# Imx6ull.net
KiCad netlist of a schematic drawn in Altium Designer
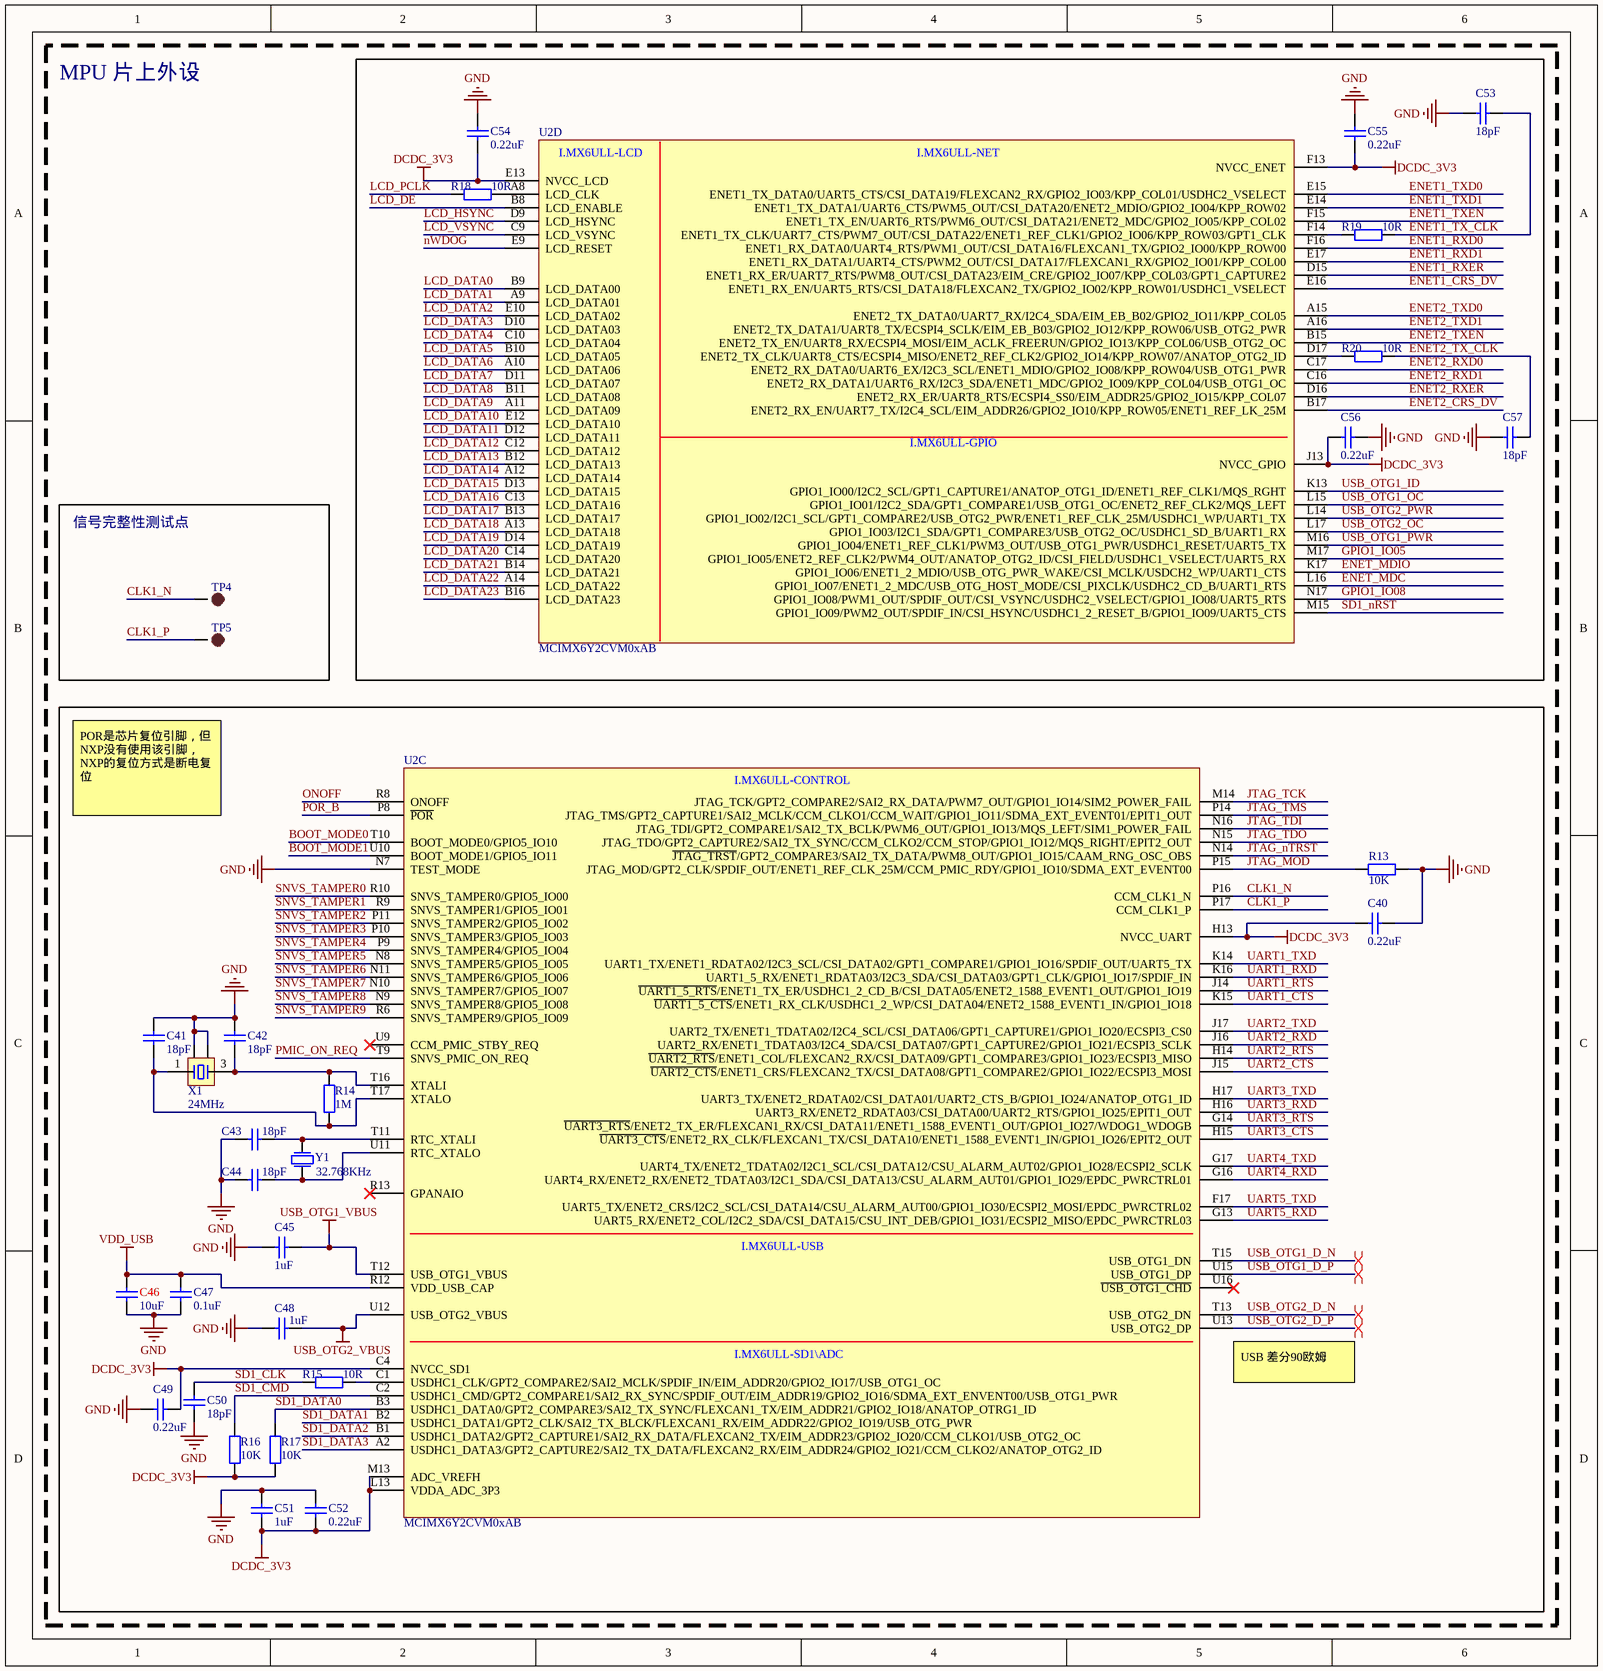
[diagram p0: Imx6ull.SchDoc]

(export (version "E")
  (design (tool "Eeschema 10.0.6"))
  (components
    (comp (ref "C40")
      (value "0.22uF")
      (footprint "0402_C")
      (description "贴片电容")
      (libsource (lib "My_Devices") (part "0402_C"))
    )
    (comp (ref "C41")
      (value "18pF")
      (footprint "0402_C")
      (description "贴片电容")
      (libsource (lib "My_Devices") (part "0402_C"))
    )
    (comp (ref "C42")
      (value "18pF")
      (footprint "0402_C")
      (description "贴片电容")
      (libsource (lib "My_Devices") (part "0402_C"))
    )
    (comp (ref "C43")
      (value "18pF")
      (footprint "0402_C")
      (description "贴片电容")
      (libsource (lib "My_Devices") (part "0402_C"))
    )
    (comp (ref "C44")
      (value "18pF")
      (footprint "0402_C")
      (description "贴片电容")
      (libsource (lib "My_Devices") (part "0402_C"))
    )
    (comp (ref "C45")
      (value "1uF")
      (footprint "0402_C")
      (description "贴片电容")
      (libsource (lib "My_Devices") (part "0402_C"))
    )
    (comp (ref "C46")
      (value "10uF")
      (footprint "0603_C _MINI")
      (description "贴片电容")
      (libsource (lib "My_Devices") (part "0603_C_MINI"))
    )
    (comp (ref "C47")
      (value "0.1uF")
      (footprint "0402_C")
      (description "贴片电容")
      (libsource (lib "My_Devices") (part "0402_C"))
    )
    (comp (ref "C48")
      (value "1uF")
      (footprint "0402_C")
      (description "贴片电容")
      (libsource (lib "My_Devices") (part "0402_C"))
    )
    (comp (ref "C49")
      (value "0.22uF")
      (footprint "0402_C")
      (description "贴片电容")
      (libsource (lib "My_Devices") (part "0402_C"))
    )
    (comp (ref "C50")
      (value "18pF")
      (footprint "0402_C")
      (description "贴片电容")
      (libsource (lib "My_Devices") (part "0402_C"))
    )
    (comp (ref "C51")
      (value "1uF")
      (footprint "0402_C")
      (description "贴片电容")
      (libsource (lib "My_Devices") (part "0402_C"))
    )
    (comp (ref "C52")
      (value "0.22uF")
      (footprint "0402_C")
      (description "贴片电容")
      (libsource (lib "My_Devices") (part "0402_C"))
    )
    (comp (ref "C53")
      (value "18pF")
      (footprint "0402_C")
      (description "贴片电容")
      (libsource (lib "My_Devices") (part "0402_C"))
    )
    (comp (ref "C54")
      (value "0.22uF")
      (footprint "0402_C")
      (description "贴片电容")
      (libsource (lib "My_Devices") (part "0402_C"))
    )
    (comp (ref "C55")
      (value "0.22uF")
      (footprint "0402_C")
      (description "贴片电容")
      (libsource (lib "My_Devices") (part "0402_C"))
    )
    (comp (ref "C56")
      (value "0.22uF")
      (footprint "0402_C")
      (description "贴片电容")
      (libsource (lib "My_Devices") (part "0402_C"))
    )
    (comp (ref "C57")
      (value "18pF")
      (footprint "0402_C")
      (description "贴片电容")
      (libsource (lib "My_Devices") (part "0402_C"))
    )
    (comp (ref "R13")
      (value "10K")
      (footprint "0402_R")
      (description "贴片电阻")
      (libsource (lib "My_Devices") (part "0402_R"))
    )
    (comp (ref "R14")
      (value "1M")
      (footprint "0402_R")
      (description "贴片电阻")
      (libsource (lib "") (part "0402_R_1"))
    )
    (comp (ref "R15")
      (value "10R")
      (footprint "0402_R")
      (description "贴片电阻")
      (libsource (lib "My_Devices") (part "0402_R"))
    )
    (comp (ref "R16")
      (value "10K")
      (footprint "0402_R")
      (description "贴片电阻")
      (libsource (lib "") (part "0402_R_2"))
    )
    (comp (ref "R17")
      (value "10K")
      (footprint "0402_R")
      (description "贴片电阻")
      (libsource (lib "") (part "0402_R_2"))
    )
    (comp (ref "R18")
      (value "10R")
      (footprint "0402_R")
      (description "贴片电阻")
      (libsource (lib "My_Devices") (part "0402_R"))
    )
    (comp (ref "R19")
      (value "10R")
      (footprint "0402_R")
      (description "贴片电阻")
      (libsource (lib "My_Devices") (part "0402_R"))
    )
    (comp (ref "R20")
      (value "10R")
      (footprint "0402_R")
      (description "贴片电阻")
      (libsource (lib "My_Devices") (part "0402_R"))
    )
    (comp (ref "TP4")
      (value "SOC_IN")
      (footprint "TP-1.0")
      (description "测试点")
      (libsource (lib "Linux_Base") (part "TEST-POINT"))
    )
    (comp (ref "TP5")
      (value "SOC_IN")
      (footprint "TP-1.0")
      (description "测试点")
      (libsource (lib "Linux_Base") (part "TEST-POINT"))
    )
    (comp (ref "U2")
      (value "MCIMX6Y2CVM0xAB")
      (footprint "BGA289_17x17_0.8Pitch")
      (libsource (lib "") (part "MCIMX6Y2CVM0xAB_1"))
    )
    (comp (ref "X1")
      (value "24MHz")
      (footprint "OSC 3225-4P")
      (description "4脚无源晶振")
      (fields (field (name "版权归属") "源创客"))
      (libsource (lib "My_Devices") (part "XTAL-4P"))
    )
    (comp (ref "Y1")
      (value "32.768KHz")
      (footprint "OSC 3215-2P")
      (description "2脚无源晶振")
      (libsource (lib "My_Devices") (part "XTAL-2P"))
    )
  )
  (nets
    (net (code "1") (name "/BOOT_MODE0") (class "Default")
      (node (ref "U2") (pin "T10") (pinfunction "BOOT_MODE0/GPIO5_IO10_T10") (pintype "passive"))
    )
    (net (code "2") (name "/BOOT_MODE1") (class "Default")
      (node (ref "U2") (pin "U10") (pinfunction "BOOT_MODE1/GPIO5_IO11_U10") (pintype "passive"))
    )
    (net (code "3") (name "/CLK1_N") (class "Default")
      (node (ref "TP4") (pin "1") (pinfunction "1_1") (pintype "passive"))
      (node (ref "U2") (pin "P16") (pinfunction "CCM_CLK1_N_P16") (pintype "passive"))
    )
    (net (code "4") (name "/CLK1_P") (class "Default")
      (node (ref "TP5") (pin "1") (pinfunction "1_1") (pintype "passive"))
      (node (ref "U2") (pin "P17") (pinfunction "CCM_CLK1_P_P17") (pintype "passive"))
    )
    (net (code "5") (name "/ENET1_CRS_DV") (class "Default")
      (node (ref "U2") (pin "E16") (pinfunction "ENET1_RX_EN/UART5_RTS/CSI_DATA18/FLEXCAN2_TX/GPIO2_IO02/KPP_ROW01/USDHC1_VSELECT_E16") (pintype "passive"))
    )
    (net (code "6") (name "/ENET1_RXD0") (class "Default")
      (node (ref "U2") (pin "F16") (pinfunction "ENET1_RX_DATA0/UART4_RTS/PWM1_OUT/CSI_DATA16/FLEXCAN1_TX/GPIO2_IO00/KPP_ROW00_F16") (pintype "passive"))
    )
    (net (code "7") (name "/ENET1_RXD1") (class "Default")
      (node (ref "U2") (pin "E17") (pinfunction "ENET1_RX_DATA1/UART4_CTS/PWM2_OUT/CSI_DATA17/FLEXCAN1_RX/GPIO2_IO01/KPP_COL00_E17") (pintype "passive"))
    )
    (net (code "8") (name "/ENET1_RXER") (class "Default")
      (node (ref "U2") (pin "D15") (pinfunction "ENET1_RX_ER/UART7_RTS/PWM8_OUT/CSI_DATA23/EIM_CRE/GPIO2_IO07/KPP_COL03/GPT1_CAPTURE2_D15") (pintype "passive"))
    )
    (net (code "9") (name "/ENET1_TXD0") (class "Default")
      (node (ref "U2") (pin "E15") (pinfunction "ENET1_TX_DATA0/UART5_CTS/CSI_DATA19/FLEXCAN2_RX/GPIO2_IO03/KPP_COL01/USDHC2_VSELECT_E15") (pintype "passive"))
    )
    (net (code "10") (name "/ENET1_TXD1") (class "Default")
      (node (ref "U2") (pin "E14") (pinfunction "ENET1_TX_DATA1/UART6_CTS/PWM5_OUT/CSI_DATA20/ENET2_MDIO/GPIO2_IO04/KPP_ROW02_E14") (pintype "passive"))
    )
    (net (code "11") (name "/ENET1_TXEN") (class "Default")
      (node (ref "U2") (pin "F15") (pinfunction "ENET1_TX_EN/UART6_RTS/PWM6_OUT/CSI_DATA21/ENET2_MDC/GPIO2_IO05/KPP_COL02_F15") (pintype "passive"))
    )
    (net (code "12") (name "/ENET1_TX_CLK") (class "Default")
      (node (ref "C53") (pin "1") (pinfunction "1_1") (pintype "passive"))
      (node (ref "R19") (pin "2") (pinfunction "2_2") (pintype "passive"))
    )
    (net (code "13") (name "/ENET2_CRS_DV") (class "Default")
      (node (ref "U2") (pin "B17") (pinfunction "ENET2_RX_EN/UART7_TX/I2C4_SCL/EIM_ADDR26/GPIO2_IO10/KPP_ROW05/ENET1_REF_LK_25M_B17") (pintype "passive"))
    )
    (net (code "14") (name "/ENET2_RXD0") (class "Default")
      (node (ref "U2") (pin "C17") (pinfunction "ENET2_RX_DATA0/UART6_EX/I2C3_SCL/ENET1_MDIO/GPIO2_IO08/KPP_ROW04/USB_OTG1_PWR_C17") (pintype "passive"))
    )
    (net (code "15") (name "/ENET2_RXD1") (class "Default")
      (node (ref "U2") (pin "C16") (pinfunction "ENET2_RX_DATA1/UART6_RX/I2C3_SDA/ENET1_MDC/GPIO2_IO09/KPP_COL04/USB_OTG1_OC_C16") (pintype "passive"))
    )
    (net (code "16") (name "/ENET2_RXER") (class "Default")
      (node (ref "U2") (pin "D16") (pinfunction "ENET2_RX_ER/UART8_RTS/ECSPI4_SS0/EIM_ADDR25/GPIO2_IO15/KPP_COL07_D16") (pintype "passive"))
    )
    (net (code "17") (name "/ENET2_TXD0") (class "Default")
      (node (ref "U2") (pin "A15") (pinfunction "ENET2_TX_DATA0/UART7_RX/I2C4_SDA/EIM_EB_B02/GPIO2_IO11/KPP_COL05_A15") (pintype "passive"))
    )
    (net (code "18") (name "/ENET2_TXD1") (class "Default")
      (node (ref "U2") (pin "A16") (pinfunction "ENET2_TX_DATA1/UART8_TX/ECSPI4_SCLK/EIM_EB_B03/GPIO2_IO12/KPP_ROW06/USB_OTG2_PWR_A16") (pintype "passive"))
    )
    (net (code "19") (name "/ENET2_TXEN") (class "Default")
      (node (ref "U2") (pin "B15") (pinfunction "ENET2_TX_EN/UART8_RX/ECSPI4_MOSI/EIM_ACLK_FREERUN/GPIO2_IO13/KPP_COL06/USB_OTG2_OC_B15") (pintype "passive"))
    )
    (net (code "20") (name "/ENET2_TX_CLK") (class "Default")
      (node (ref "C57") (pin "2") (pinfunction "2_2") (pintype "passive"))
      (node (ref "R20") (pin "2") (pinfunction "2_2") (pintype "passive"))
    )
    (net (code "21") (name "/ENET_MDC") (class "Default")
      (node (ref "U2") (pin "L16") (pinfunction "GPIO1_IO07/ENET1_2_MDC/USB_OTG_HOST_MODE/CSI_PIXCLK/USDHC2_CD_B/UART1_RTS_L16") (pintype "passive"))
    )
    (net (code "22") (name "/ENET_MDIO") (class "Default")
      (node (ref "U2") (pin "K17") (pinfunction "GPIO1_IO06/ENET1_2_MDIO/USB_OTG_PWR_WAKE/CSI_MCLK/USDCH2_WP/UART1_CTS_K17") (pintype "passive"))
    )
    (net (code "23") (name "/GPIO1_IO05") (class "Default")
      (node (ref "U2") (pin "M17") (pinfunction "GPIO1_IO05/ENET2_REF_CLK2/PWM4_OUT/ANATOP_OTG2_ID/CSI_FIELD/USDHC1_VSELECT/UART5_RX_M17") (pintype "passive"))
    )
    (net (code "24") (name "/GPIO1_IO08") (class "Default")
      (node (ref "U2") (pin "N17") (pinfunction "GPIO1_IO08/PWM1_OUT/SPDIF_OUT/CSI_VSYNC/USDHC2_VSELECT/GPIO1_IO08/UART5_RTS_N17") (pintype "passive"))
    )
    (net (code "25") (name "/JTAG_MOD") (class "Default")
      (node (ref "R13") (pin "1") (pinfunction "1_1") (pintype "passive"))
      (node (ref "U2") (pin "P15") (pinfunction "JTAG_MOD/GPT2_CLK/SPDIF_OUT/ENET1_REF_CLK_25M/CCM_PMIC_RDY/GPIO1_IO10/SDMA_EXT_EVENT00_P15") (pintype "passive"))
    )
    (net (code "26") (name "/JTAG_TCK") (class "Default")
      (node (ref "U2") (pin "M14") (pinfunction "JTAG_TCK/GPT2_COMPARE2/SAI2_RX_DATA/PWM7_OUT/GPIO1_IO14/SIM2_POWER_FAIL_M14") (pintype "passive"))
    )
    (net (code "27") (name "/JTAG_TDI") (class "Default")
      (node (ref "U2") (pin "N16") (pinfunction "JTAG_TDI/GPT2_COMPARE1/SAI2_TX_BCLK/PWM6_OUT/GPIO1_IO13/MQS_LEFT/SIM1_POWER_FAIL_N16") (pintype "passive"))
    )
    (net (code "28") (name "/JTAG_TDO") (class "Default")
      (node (ref "U2") (pin "N15") (pinfunction "JTAG_TDO/GPT2_CAPTURE2/SAI2_TX_SYNC/CCM_CLKO2/CCM_STOP/GPIO1_IO12/MQS_RIGHT/EPIT2_OUT_N15") (pintype "passive"))
    )
    (net (code "29") (name "/JTAG_TMS") (class "Default")
      (node (ref "U2") (pin "P14") (pinfunction "JTAG_TMS/GPT2_CAPTURE1/SAI2_MCLK/CCM_CLKO1/CCM_WAIT/GPIO1_IO11/SDMA_EXT_EVENT01/EPIT1_OUT_P14") (pintype "passive"))
    )
    (net (code "30") (name "/JTAG_nTRST") (class "Default")
      (node (ref "U2") (pin "N14") (pinfunction "~{JTAG_TRST}/GPT2_COMPARE3/SAI2_TX_DATA/PWM8_OUT/GPIO1_IO15/CAAM_RNG_OSC_OBS_N14") (pintype "passive"))
    )
    (net (code "31") (name "/LCD_DATA0") (class "Default")
      (node (ref "U2") (pin "B9") (pinfunction "LCD_DATA00_B9") (pintype "passive"))
    )
    (net (code "32") (name "/LCD_DATA1") (class "Default")
      (node (ref "U2") (pin "A9") (pinfunction "LCD_DATA01_A9") (pintype "passive"))
    )
    (net (code "33") (name "/LCD_DATA2") (class "Default")
      (node (ref "U2") (pin "E10") (pinfunction "LCD_DATA02_E10") (pintype "passive"))
    )
    (net (code "34") (name "/LCD_DATA3") (class "Default")
      (node (ref "U2") (pin "D10") (pinfunction "LCD_DATA03_D10") (pintype "passive"))
    )
    (net (code "35") (name "/LCD_DATA4") (class "Default")
      (node (ref "U2") (pin "C10") (pinfunction "LCD_DATA04_C10") (pintype "passive"))
    )
    (net (code "36") (name "/LCD_DATA5") (class "Default")
      (node (ref "U2") (pin "B10") (pinfunction "LCD_DATA05_B10") (pintype "passive"))
    )
    (net (code "37") (name "/LCD_DATA6") (class "Default")
      (node (ref "U2") (pin "A10") (pinfunction "LCD_DATA06_A10") (pintype "passive"))
    )
    (net (code "38") (name "/LCD_DATA7") (class "Default")
      (node (ref "U2") (pin "D11") (pinfunction "LCD_DATA07_D11") (pintype "passive"))
    )
    (net (code "39") (name "/LCD_DATA8") (class "Default")
      (node (ref "U2") (pin "B11") (pinfunction "LCD_DATA08_B11") (pintype "passive"))
    )
    (net (code "40") (name "/LCD_DATA9") (class "Default")
      (node (ref "U2") (pin "A11") (pinfunction "LCD_DATA09_A11") (pintype "passive"))
    )
    (net (code "41") (name "/LCD_DATA10") (class "Default")
      (node (ref "U2") (pin "E12") (pinfunction "LCD_DATA10_E12") (pintype "passive"))
    )
    (net (code "42") (name "/LCD_DATA11") (class "Default")
      (node (ref "U2") (pin "D12") (pinfunction "LCD_DATA11_D12") (pintype "passive"))
    )
    (net (code "43") (name "/LCD_DATA12") (class "Default")
      (node (ref "U2") (pin "C12") (pinfunction "LCD_DATA12_C12") (pintype "passive"))
    )
    (net (code "44") (name "/LCD_DATA13") (class "Default")
      (node (ref "U2") (pin "B12") (pinfunction "LCD_DATA13_B12") (pintype "passive"))
    )
    (net (code "45") (name "/LCD_DATA14") (class "Default")
      (node (ref "U2") (pin "A12") (pinfunction "LCD_DATA14_A12") (pintype "passive"))
    )
    (net (code "46") (name "/LCD_DATA15") (class "Default")
      (node (ref "U2") (pin "D13") (pinfunction "LCD_DATA15_D13") (pintype "passive"))
    )
    (net (code "47") (name "/LCD_DATA16") (class "Default")
      (node (ref "U2") (pin "C13") (pinfunction "LCD_DATA16_C13") (pintype "passive"))
    )
    (net (code "48") (name "/LCD_DATA17") (class "Default")
      (node (ref "U2") (pin "B13") (pinfunction "LCD_DATA17_B13") (pintype "passive"))
    )
    (net (code "49") (name "/LCD_DATA18") (class "Default")
      (node (ref "U2") (pin "A13") (pinfunction "LCD_DATA18_A13") (pintype "passive"))
    )
    (net (code "50") (name "/LCD_DATA19") (class "Default")
      (node (ref "U2") (pin "D14") (pinfunction "LCD_DATA19_D14") (pintype "passive"))
    )
    (net (code "51") (name "/LCD_DATA20") (class "Default")
      (node (ref "U2") (pin "C14") (pinfunction "LCD_DATA20_C14") (pintype "passive"))
    )
    (net (code "52") (name "/LCD_DATA21") (class "Default")
      (node (ref "U2") (pin "B14") (pinfunction "LCD_DATA21_B14") (pintype "passive"))
    )
    (net (code "53") (name "/LCD_DATA22") (class "Default")
      (node (ref "U2") (pin "A14") (pinfunction "LCD_DATA22_A14") (pintype "passive"))
    )
    (net (code "54") (name "/LCD_DATA23") (class "Default")
      (node (ref "U2") (pin "B16") (pinfunction "LCD_DATA23_B16") (pintype "passive"))
    )
    (net (code "55") (name "/LCD_DE") (class "Default")
      (node (ref "U2") (pin "B8") (pinfunction "LCD_ENABLE_B8") (pintype "passive"))
    )
    (net (code "56") (name "/LCD_HSYNC") (class "Default")
      (node (ref "U2") (pin "D9") (pinfunction "LCD_HSYNC_D9") (pintype "passive"))
    )
    (net (code "57") (name "/LCD_PCLK") (class "Default")
      (node (ref "R18") (pin "1") (pinfunction "1_1") (pintype "passive"))
    )
    (net (code "58") (name "/LCD_VSYNC") (class "Default")
      (node (ref "U2") (pin "C9") (pinfunction "LCD_VSYNC_C9") (pintype "passive"))
    )
    (net (code "59") (name "/ONOFF") (class "Default")
      (node (ref "U2") (pin "R8") (pinfunction "ONOFF_R8") (pintype "passive"))
    )
    (net (code "60") (name "/PMIC_ON_REQ") (class "Default")
      (node (ref "U2") (pin "T9") (pinfunction "SNVS_PMIC_ON_REQ_T9") (pintype "passive"))
    )
    (net (code "61") (name "/POR_B") (class "Default")
      (node (ref "U2") (pin "P8") (pinfunction "~{POR}_P8") (pintype "passive"))
    )
    (net (code "62") (name "/SD1_CLK") (class "Default")
      (node (ref "C50") (pin "2") (pinfunction "2_2") (pintype "passive"))
      (node (ref "R15") (pin "1") (pinfunction "1_1") (pintype "passive"))
    )
    (net (code "63") (name "/SD1_CMD") (class "Default")
      (node (ref "R16") (pin "2") (pinfunction "2_2") (pintype "passive"))
      (node (ref "U2") (pin "C2") (pinfunction "USDHC1_CMD/GPT2_COMPARE1/SAI2_RX_SYNC/SPDIF_OUT/EIM_ADDR19/GPIO2_IO16/SDMA_EXT_ENVENT00/USB_OTG1_PWR_C2") (pintype "passive"))
    )
    (net (code "64") (name "/SD1_DATA0") (class "Default")
      (node (ref "R17") (pin "2") (pinfunction "2_2") (pintype "passive"))
      (node (ref "U2") (pin "B3") (pinfunction "USDHC1_DATA0/GPT2_COMPARE3/SAI2_TX_SYNC/FLEXCAN1_TX/EIM_ADDR21/GPIO2_IO18/ANATOP_OTRG1_ID_B3") (pintype "passive"))
    )
    (net (code "65") (name "/SD1_DATA1") (class "Default")
      (node (ref "U2") (pin "B2") (pinfunction "USDHC1_DATA1/GPT2_CLK/SAI2_TX_BLCK/FLEXCAN1_RX/EIM_ADDR22/GPIO2_IO19/USB_OTG_PWR_B2") (pintype "passive"))
    )
    (net (code "66") (name "/SD1_DATA2") (class "Default")
      (node (ref "U2") (pin "B1") (pinfunction "USDHC1_DATA2/GPT2_CAPTURE1/SAI2_RX_DATA/FLEXCAN2_TX/EIM_ADDR23/GPIO2_IO20/CCM_CLKO1/USB_OTG2_OC_B1") (pintype "passive"))
    )
    (net (code "67") (name "/SD1_DATA3") (class "Default")
      (node (ref "U2") (pin "A2") (pinfunction "USDHC1_DATA3/GPT2_CAPTURE2/SAI2_TX_DATA/FLEXCAN2_RX/EIM_ADDR24/GPIO2_IO21/CCM_CLKO2/ANATOP_OTG2_ID_A2") (pintype "passive"))
    )
    (net (code "68") (name "/SD1_nRST") (class "Default")
      (node (ref "U2") (pin "M15") (pinfunction "GPIO1_IO09/PWM2_OUT/SPDIF_IN/CSI_HSYNC/USDHC1_2_RESET_B/GPIO1_IO09/UART5_CTS_M15") (pintype "passive"))
    )
    (net (code "69") (name "/SNVS_TAMPER0") (class "Default")
      (node (ref "U2") (pin "R10") (pinfunction "SNVS_TAMPER0/GPIO5_IO00_R10") (pintype "passive"))
    )
    (net (code "70") (name "/SNVS_TAMPER1") (class "Default")
      (node (ref "U2") (pin "R9") (pinfunction "SNVS_TAMPER1/GPIO5_IO01_R9") (pintype "passive"))
    )
    (net (code "71") (name "/SNVS_TAMPER2") (class "Default")
      (node (ref "U2") (pin "P11") (pinfunction "SNVS_TAMPER2/GPIO5_IO02_P11") (pintype "passive"))
    )
    (net (code "72") (name "/SNVS_TAMPER3") (class "Default")
      (node (ref "U2") (pin "P10") (pinfunction "SNVS_TAMPER3/GPIO5_IO03_P10") (pintype "passive"))
    )
    (net (code "73") (name "/SNVS_TAMPER4") (class "Default")
      (node (ref "U2") (pin "P9") (pinfunction "SNVS_TAMPER4/GPIO5_IO04_P9") (pintype "passive"))
    )
    (net (code "74") (name "/SNVS_TAMPER5") (class "Default")
      (node (ref "U2") (pin "N8") (pinfunction "SNVS_TAMPER5/GPIO5_IO05_N8") (pintype "passive"))
    )
    (net (code "75") (name "/SNVS_TAMPER6") (class "Default")
      (node (ref "U2") (pin "N11") (pinfunction "SNVS_TAMPER6/GPIO5_IO06_N11") (pintype "passive"))
    )
    (net (code "76") (name "/SNVS_TAMPER7") (class "Default")
      (node (ref "U2") (pin "N10") (pinfunction "SNVS_TAMPER7/GPIO5_IO07_N10") (pintype "passive"))
    )
    (net (code "77") (name "/SNVS_TAMPER8") (class "Default")
      (node (ref "U2") (pin "N9") (pinfunction "SNVS_TAMPER8/GPIO5_IO08_N9") (pintype "passive"))
    )
    (net (code "78") (name "/SNVS_TAMPER9") (class "Default")
      (node (ref "U2") (pin "R6") (pinfunction "SNVS_TAMPER9/GPIO5_IO09_R6") (pintype "passive"))
    )
    (net (code "79") (name "/UART1_CTS") (class "Default")
      (node (ref "U2") (pin "K15") (pinfunction "~{UART1_5_CTS}/ENET1_RX_CLK/USDHC1_2_WP/CSI_DATA04/ENET2_1588_EVENT1_IN/GPIO1_IO18_K15") (pintype "passive"))
    )
    (net (code "80") (name "/UART1_RTS") (class "Default")
      (node (ref "U2") (pin "J14") (pinfunction "~{UART1_5_RTS}/ENET1_TX_ER/USDHC1_2_CD_B/CSI_DATA05/ENET2_1588_EVENT1_OUT/GPIO1_IO19_J14") (pintype "passive"))
    )
    (net (code "81") (name "/UART1_RXD") (class "Default")
      (node (ref "U2") (pin "K16") (pinfunction "UART1_5_RX/ENET1_RDATA03/I2C3_SDA/CSI_DATA03/GPT1_CLK/GPIO1_IO17/SPDIF_IN_K16") (pintype "passive"))
    )
    (net (code "82") (name "/UART1_TXD") (class "Default")
      (node (ref "U2") (pin "K14") (pinfunction "UART1_TX/ENET1_RDATA02/I2C3_SCL/CSI_DATA02/GPT1_COMPARE1/GPIO1_IO16/SPDIF_OUT/UART5_TX_K14") (pintype "passive"))
    )
    (net (code "83") (name "/UART2_CTS") (class "Default")
      (node (ref "U2") (pin "J15") (pinfunction "~{UART2_CTS}/ENET1_CRS/FLEXCAN2_TX/CSI_DATA08/GPT1_COMPARE2/GPIO1_IO22/ECSPI3_MOSI_J15") (pintype "passive"))
    )
    (net (code "84") (name "/UART2_RTS") (class "Default")
      (node (ref "U2") (pin "H14") (pinfunction "~{UART2_RTS}/ENET1_COL/FLEXCAN2_RX/CSI_DATA09/GPT1_COMPARE3/GPIO1_IO23/ECSPI3_MISO_H14") (pintype "passive"))
    )
    (net (code "85") (name "/UART2_RXD") (class "Default")
      (node (ref "U2") (pin "J16") (pinfunction "UART2_RX/ENET1_TDATA03/I2C4_SDA/CSI_DATA07/GPT1_CAPTURE2/GPIO1_IO21/ECSPI3_SCLK_J16") (pintype "passive"))
    )
    (net (code "86") (name "/UART2_TXD") (class "Default")
      (node (ref "U2") (pin "J17") (pinfunction "UART2_TX/ENET1_TDATA02/I2C4_SCL/CSI_DATA06/GPT1_CAPTURE1/GPIO1_IO20/ECSPI3_CS0_J17") (pintype "passive"))
    )
    (net (code "87") (name "/UART3_CTS") (class "Default")
      (node (ref "U2") (pin "H15") (pinfunction "~{UART3_CTS}/ENET2_RX_CLK/FLEXCAN1_TX/CSI_DATA10/ENET1_1588_EVENT1_IN/GPIO1_IO26/EPIT2_OUT_H15") (pintype "passive"))
    )
    (net (code "88") (name "/UART3_RTS") (class "Default")
      (node (ref "U2") (pin "G14") (pinfunction "~{UART3_RTS}/ENET2_TX_ER/FLEXCAN1_RX/CSI_DATA11/ENET1_1588_EVENT1_OUT/GPIO1_IO27/WDOG1_WDOGB_G14") (pintype "passive"))
    )
    (net (code "89") (name "/UART3_RXD") (class "Default")
      (node (ref "U2") (pin "H16") (pinfunction "UART3_RX/ENET2_RDATA03/CSI_DATA00/UART2_RTS/GPIO1_IO25/EPIT1_OUT_H16") (pintype "passive"))
    )
    (net (code "90") (name "/UART3_TXD") (class "Default")
      (node (ref "U2") (pin "H17") (pinfunction "UART3_TX/ENET2_RDATA02/CSI_DATA01/UART2_CTS_B/GPIO1_IO24/ANATOP_OTG1_ID_H17") (pintype "passive"))
    )
    (net (code "91") (name "/UART4_RXD") (class "Default")
      (node (ref "U2") (pin "G16") (pinfunction "UART4_RX/ENET2_RX/ENET2_TDATA03/I2C1_SDA/CSI_DATA13/CSU_ALARM_AUT01/GPIO1_IO29/EPDC_PWRCTRL01_G16") (pintype "passive"))
    )
    (net (code "92") (name "/UART4_TXD") (class "Default")
      (node (ref "U2") (pin "G17") (pinfunction "UART4_TX/ENET2_TDATA02/I2C1_SCL/CSI_DATA12/CSU_ALARM_AUT02/GPIO1_IO28/ECSPI2_SCLK_G17") (pintype "passive"))
    )
    (net (code "93") (name "/UART5_RXD") (class "Default")
      (node (ref "U2") (pin "G13") (pinfunction "UART5_RX/ENET2_COL/I2C2_SDA/CSI_DATA15/CSU_INT_DEB/GPIO1_IO31/ECSPI2_MISO/EPDC_PWRCTRL03_G13") (pintype "passive"))
    )
    (net (code "94") (name "/UART5_TXD") (class "Default")
      (node (ref "U2") (pin "F17") (pinfunction "UART5_TX/ENET2_CRS/I2C2_SCL/CSI_DATA14/CSU_ALARM_AUT00/GPIO1_IO30/ECSPI2_MOSI/EPDC_PWRCTRL02_F17") (pintype "passive"))
    )
    (net (code "95") (name "/USB_OTG1_D_N") (class "Default")
      (node (ref "U2") (pin "T15") (pinfunction "USB_OTG1_DN_T15") (pintype "passive"))
    )
    (net (code "96") (name "/USB_OTG1_D_P") (class "Default")
      (node (ref "U2") (pin "U15") (pinfunction "USB_OTG1_DP_U15") (pintype "passive"))
    )
    (net (code "97") (name "/USB_OTG1_ID") (class "Default")
      (node (ref "U2") (pin "K13") (pinfunction "GPIO1_IO00/I2C2_SCL/GPT1_CAPTURE1/ANATOP_OTG1_ID/ENET1_REF_CLK1/MQS_RGHT_K13") (pintype "passive"))
    )
    (net (code "98") (name "/USB_OTG1_OC") (class "Default")
      (node (ref "U2") (pin "L15") (pinfunction "GPIO1_IO01/I2C2_SDA/GPT1_COMPARE1/USB_OTG1_OC/ENET2_REF_CLK2/MQS_LEFT_L15") (pintype "passive"))
    )
    (net (code "99") (name "/USB_OTG1_PWR") (class "Default")
      (node (ref "U2") (pin "M16") (pinfunction "GPIO1_IO04/ENET1_REF_CLK1/PWM3_OUT/USB_OTG1_PWR/USDHC1_RESET/UART5_TX_M16") (pintype "passive"))
    )
    (net (code "100") (name "/USB_OTG2_D_N") (class "Default")
      (node (ref "U2") (pin "T13") (pinfunction "USB_OTG2_DN_T13") (pintype "passive"))
    )
    (net (code "101") (name "/USB_OTG2_D_P") (class "Default")
      (node (ref "U2") (pin "U13") (pinfunction "USB_OTG2_DP_U13") (pintype "passive"))
    )
    (net (code "102") (name "/USB_OTG2_OC") (class "Default")
      (node (ref "U2") (pin "L17") (pinfunction "GPIO1_IO03/I2C1_SDA/GPT1_COMPARE3/USB_OTG2_OC/USDHC1_SD_B/UART1_RX_L17") (pintype "passive"))
    )
    (net (code "103") (name "/USB_OTG2_PWR") (class "Default")
      (node (ref "U2") (pin "L14") (pinfunction "GPIO1_IO02/I2C1_SCL/GPT1_COMPARE2/USB_OTG2_PWR/ENET1_REF_CLK_25M/USDHC1_WP/UART1_TX_L14") (pintype "passive"))
    )
    (net (code "104") (name "/nWDOG") (class "Default")
      (node (ref "U2") (pin "E9") (pinfunction "LCD_RESET_E9") (pintype "passive"))
    )
    (net (code "105") (name "DCDC_3V3") (class "Default")
      (node (ref "C40") (pin "1") (pinfunction "1_1") (pintype "passive"))
      (node (ref "C49") (pin "2") (pinfunction "2_2") (pintype "passive"))
      (node (ref "C51") (pin "1") (pinfunction "1_1") (pintype "passive"))
      (node (ref "C52") (pin "1") (pinfunction "1_1") (pintype "passive"))
      (node (ref "C54") (pin "1") (pinfunction "1_1") (pintype "passive"))
      (node (ref "C55") (pin "1") (pinfunction "1_1") (pintype "passive"))
      (node (ref "C56") (pin "1") (pinfunction "1_1") (pintype "passive"))
      (node (ref "R16") (pin "1") (pinfunction "1_1") (pintype "passive"))
      (node (ref "R17") (pin "1") (pinfunction "1_1") (pintype "passive"))
      (node (ref "U2") (pin "C4") (pinfunction "NVCC_SD1_C4") (pintype "passive"))
      (node (ref "U2") (pin "E13") (pinfunction "NVCC_LCD_E13") (pintype "passive"))
      (node (ref "U2") (pin "F13") (pinfunction "NVCC_ENET_F13") (pintype "passive"))
      (node (ref "U2") (pin "H13") (pinfunction "NVCC_UART_H13") (pintype "passive"))
      (node (ref "U2") (pin "J13") (pinfunction "NVCC_GPIO_J13") (pintype "passive"))
      (node (ref "U2") (pin "L13") (pinfunction "VDDA_ADC_3P3_L13") (pintype "passive"))
      (node (ref "U2") (pin "M13") (pinfunction "ADC_VREFH_M13") (pintype "passive"))
    )
    (net (code "106") (name "GND") (class "Default")
      (node (ref "C40") (pin "2") (pinfunction "2_2") (pintype "passive"))
      (node (ref "C41") (pin "2") (pinfunction "2_2") (pintype "passive"))
      (node (ref "C42") (pin "2") (pinfunction "2_2") (pintype "passive"))
      (node (ref "C43") (pin "1") (pinfunction "1_1") (pintype "passive"))
      (node (ref "C44") (pin "1") (pinfunction "1_1") (pintype "passive"))
      (node (ref "C45") (pin "1") (pinfunction "1_1") (pintype "passive"))
      (node (ref "C46") (pin "1") (pinfunction "1_1") (pintype "passive"))
      (node (ref "C47") (pin "1") (pinfunction "1_1") (pintype "passive"))
      (node (ref "C48") (pin "1") (pinfunction "1_1") (pintype "passive"))
      (node (ref "C49") (pin "1") (pinfunction "1_1") (pintype "passive"))
      (node (ref "C50") (pin "1") (pinfunction "1_1") (pintype "passive"))
      (node (ref "C51") (pin "2") (pinfunction "2_2") (pintype "passive"))
      (node (ref "C52") (pin "2") (pinfunction "2_2") (pintype "passive"))
      (node (ref "C53") (pin "2") (pinfunction "2_2") (pintype "passive"))
      (node (ref "C54") (pin "2") (pinfunction "2_2") (pintype "passive"))
      (node (ref "C55") (pin "2") (pinfunction "2_2") (pintype "passive"))
      (node (ref "C56") (pin "2") (pinfunction "2_2") (pintype "passive"))
      (node (ref "C57") (pin "1") (pinfunction "1_1") (pintype "passive"))
      (node (ref "R13") (pin "2") (pinfunction "2_2") (pintype "passive"))
      (node (ref "U2") (pin "N7") (pinfunction "TEST_MODE_N7") (pintype "passive"))
      (node (ref "X1") (pin "2") (pinfunction "2_2") (pintype "passive"))
      (node (ref "X1") (pin "4") (pinfunction "4_4") (pintype "passive"))
    )
    (net (code "107") (name "Net-(U2C-RTC_XTALI)") (class "Default")
      (node (ref "C43") (pin "2") (pinfunction "2_2") (pintype "passive"))
      (node (ref "U2") (pin "T11") (pinfunction "RTC_XTALI_T11") (pintype "passive"))
      (node (ref "Y1") (pin "2") (pinfunction "P2_2") (pintype "passive"))
    )
    (net (code "108") (name "Net-(U2C-RTC_XTALO)") (class "Default")
      (node (ref "C44") (pin "2") (pinfunction "2_2") (pintype "passive"))
      (node (ref "U2") (pin "U11") (pinfunction "RTC_XTALO_U11") (pintype "passive"))
      (node (ref "Y1") (pin "1") (pinfunction "P1_1") (pintype "passive"))
    )
    (net (code "109") (name "Net-(U2C-USDHC1_CLK{slash}GPT2_COMPARE2{slash}SAI2_MCLK{slash}SPDIF_IN{slash}EIM_ADDR20{slash}GPIO2_IO17{slash}USB_OTG1_OC)") (class "Default")
      (node (ref "R15") (pin "2") (pinfunction "2_2") (pintype "passive"))
      (node (ref "U2") (pin "C1") (pinfunction "USDHC1_CLK/GPT2_COMPARE2/SAI2_MCLK/SPDIF_IN/EIM_ADDR20/GPIO2_IO17/USB_OTG1_OC_C1") (pintype "passive"))
    )
    (net (code "110") (name "Net-(U2C-XTALI)") (class "Default")
      (node (ref "C42") (pin "1") (pinfunction "1_1") (pintype "passive"))
      (node (ref "R14") (pin "1") (pinfunction "1_1") (pintype "passive"))
      (node (ref "U2") (pin "T16") (pinfunction "XTALI_T16") (pintype "passive"))
      (node (ref "X1") (pin "3") (pinfunction "3_3") (pintype "passive"))
    )
    (net (code "111") (name "Net-(U2C-XTALO)") (class "Default")
      (node (ref "C41") (pin "1") (pinfunction "1_1") (pintype "passive"))
      (node (ref "R14") (pin "2") (pinfunction "2_2") (pintype "passive"))
      (node (ref "U2") (pin "T17") (pinfunction "XTALO_T17") (pintype "passive"))
      (node (ref "X1") (pin "1") (pinfunction "1_1") (pintype "passive"))
    )
    (net (code "112") (name "Net-(U2D-ENET1_TX_CLK{slash}UART7_CTS{slash}PWM7_OUT{slash}CSI_DATA22{slash}ENET1_REF_CLK1{slash}GPIO2_IO06{slash}KPP_ROW03{slash}GPT1_CLK)") (class "Default")
      (node (ref "R19") (pin "1") (pinfunction "1_1") (pintype "passive"))
      (node (ref "U2") (pin "F14") (pinfunction "ENET1_TX_CLK/UART7_CTS/PWM7_OUT/CSI_DATA22/ENET1_REF_CLK1/GPIO2_IO06/KPP_ROW03/GPT1_CLK_F14") (pintype "passive"))
    )
    (net (code "113") (name "Net-(U2D-ENET2_TX_CLK{slash}UART8_CTS{slash}ECSPI4_MISO{slash}ENET2_REF_CLK2{slash}GPIO2_IO14{slash}KPP_ROW07{slash}ANATOP_OTG2_ID)") (class "Default")
      (node (ref "R20") (pin "1") (pinfunction "1_1") (pintype "passive"))
      (node (ref "U2") (pin "D17") (pinfunction "ENET2_TX_CLK/UART8_CTS/ECSPI4_MISO/ENET2_REF_CLK2/GPIO2_IO14/KPP_ROW07/ANATOP_OTG2_ID_D17") (pintype "passive"))
    )
    (net (code "114") (name "Net-(U2D-LCD_CLK)") (class "Default")
      (node (ref "R18") (pin "2") (pinfunction "2_2") (pintype "passive"))
      (node (ref "U2") (pin "A8") (pinfunction "LCD_CLK_A8") (pintype "passive"))
    )
    (net (code "115") (name "USB_OTG1_VBUS") (class "Default")
      (node (ref "C45") (pin "2") (pinfunction "2_2") (pintype "passive"))
      (node (ref "U2") (pin "T12") (pinfunction "USB_OTG1_VBUS_T12") (pintype "passive"))
    )
    (net (code "116") (name "USB_OTG2_VBUS") (class "Default")
      (node (ref "C48") (pin "2") (pinfunction "2_2") (pintype "passive"))
      (node (ref "U2") (pin "U12") (pinfunction "USB_OTG2_VBUS_U12") (pintype "passive"))
    )
    (net (code "117") (name "VDD_USB") (class "Default")
      (node (ref "C46") (pin "2") (pinfunction "2_2") (pintype "passive"))
      (node (ref "C47") (pin "2") (pinfunction "2_2") (pintype "passive"))
      (node (ref "U2") (pin "R12") (pinfunction "VDD_USB_CAP_R12") (pintype "passive"))
    )
    (net (code "118") (name "unconnected-(U2C-CCM_PMIC_STBY_REQ-PadU9)") (class "Default")
      (node (ref "U2") (pin "U9") (pinfunction "CCM_PMIC_STBY_REQ_U9") (pintype "passive+no_connect"))
    )
    (net (code "119") (name "unconnected-(U2C-GPANAIO-PadR13)") (class "Default")
      (node (ref "U2") (pin "R13") (pinfunction "GPANAIO_R13") (pintype "passive+no_connect"))
    )
    (net (code "120") (name "unconnected-(U2C-~{USB_OTG1_CHD}-PadU16)") (class "Default")
      (node (ref "U2") (pin "U16") (pinfunction "~{USB_OTG1_CHD}_U16") (pintype "passive+no_connect"))
    )
  )
)
